# irisc.net
KiCad netlist of a schematic drawn in EAGLE
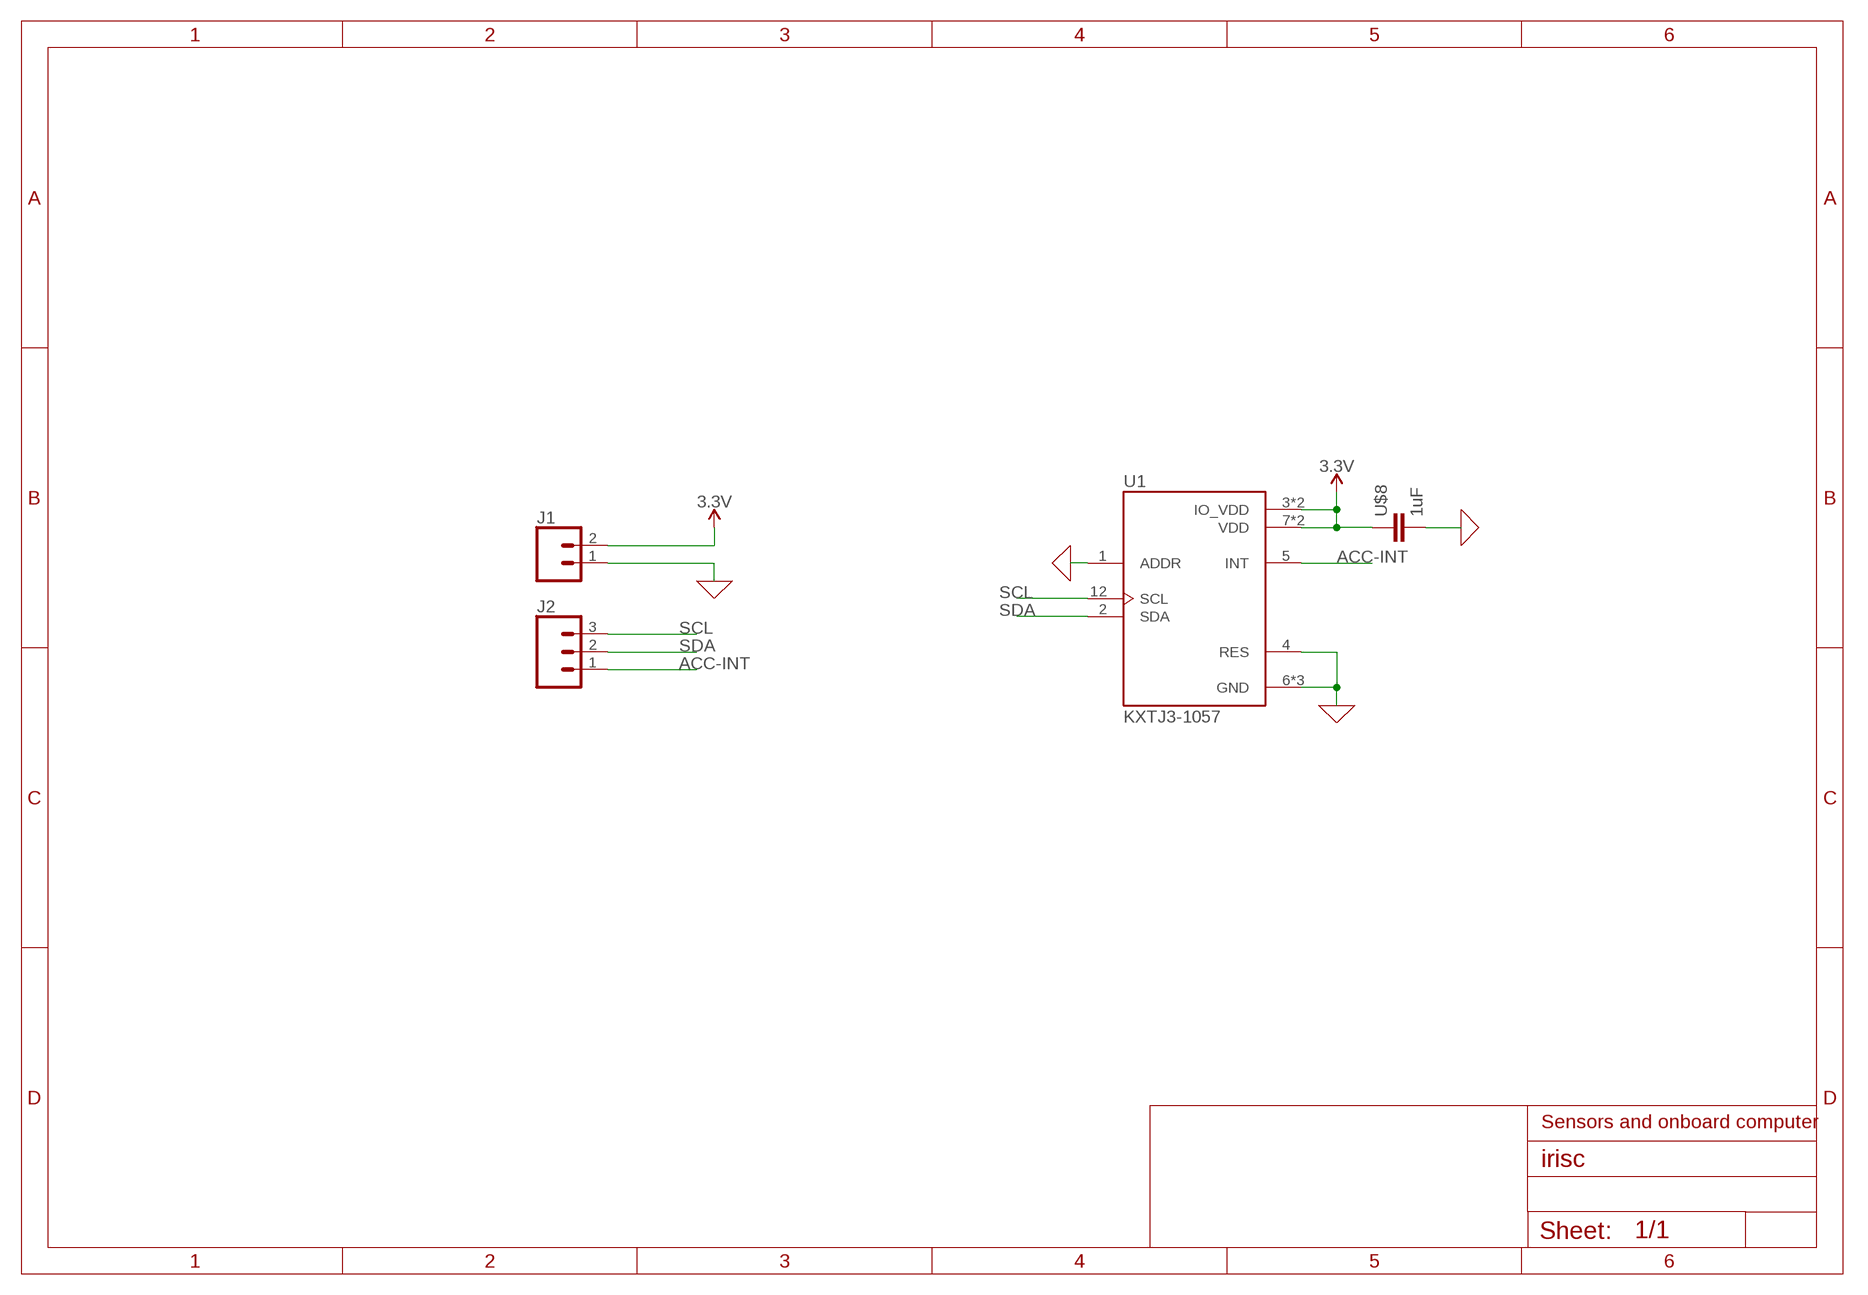
[diagram p0: schematic, sheet 1]

(export (version "E")
  (design (tool "Eeschema 10.0.6"))
  (components
    (comp (ref "J1")
      (value "CONN_02")
      (footprint "eagle-import:1X02")
      (libsource (lib "eagle-import") (part "CONN_02"))
    )
    (comp (ref "J2")
      (value "CONN_03")
      (footprint "eagle-import:1X03")
      (libsource (lib "eagle-import") (part "CONN_03"))
    )
    (comp (ref "U$8")
      (value "1uF")
      (footprint "eagle-import:RESC0603_N")
      (libsource (lib "eagle-import") (part "CAPACITOR_0603_N"))
    )
    (comp (ref "U1")
      (value "KXTJ3-1057")
      (footprint "eagle-import:KIONIX_KXTJ3-1057")
      (fields (field (name "MF") "Kionix Inc."))
      (libsource (lib "eagle-import") (part "KXTJ3-1057"))
    )
  )
  (nets
    (net (code "1") (name "/ACC-INT") (class "Default")
      (node (ref "J2") (pin "1") (pinfunction "1_1") (pintype "passive"))
      (node (ref "U1") (pin "5") (pinfunction "INT_5") (pintype "output"))
    )
    (net (code "2") (name "/SCL") (class "Default")
      (node (ref "J2") (pin "3") (pinfunction "3_3") (pintype "passive"))
      (node (ref "U1") (pin "12") (pinfunction "SCL_12") (pintype "input"))
    )
    (net (code "3") (name "/SDA") (class "Default")
      (node (ref "J2") (pin "2") (pinfunction "2_2") (pintype "passive"))
      (node (ref "U1") (pin "2") (pinfunction "SDA_2") (pintype "bidirectional"))
    )
    (net (code "4") (name "3.3V") (class "Default")
      (node (ref "J1") (pin "2") (pinfunction "2_2") (pintype "passive"))
      (node (ref "U$8") (pin "1") (pinfunction "1_1") (pintype "passive"))
      (node (ref "U1") (pin "10") (pinfunction "VDD_10") (pintype "power_in"))
      (node (ref "U1") (pin "11") (pinfunction "IO_VDD_11") (pintype "power_in"))
      (node (ref "U1") (pin "3") (pinfunction "IO_VDD_3") (pintype "power_in"))
      (node (ref "U1") (pin "7") (pinfunction "VDD_7") (pintype "power_in"))
    )
    (net (code "5") (name "GND") (class "Default")
      (node (ref "J1") (pin "1") (pinfunction "1_1") (pintype "passive"))
      (node (ref "U$8") (pin "2") (pinfunction "2_2") (pintype "passive"))
      (node (ref "U1") (pin "1") (pinfunction "ADDR_1") (pintype "input"))
      (node (ref "U1") (pin "4") (pinfunction "RES_4") (pintype "passive"))
      (node (ref "U1") (pin "6") (pinfunction "GND_6") (pintype "power_in"))
      (node (ref "U1") (pin "8") (pinfunction "GND_8") (pintype "power_in"))
      (node (ref "U1") (pin "9") (pinfunction "GND_9") (pintype "power_in"))
    )
  )
)
